# Cell.net
KiCad netlist of a schematic drawn in Altium Designer
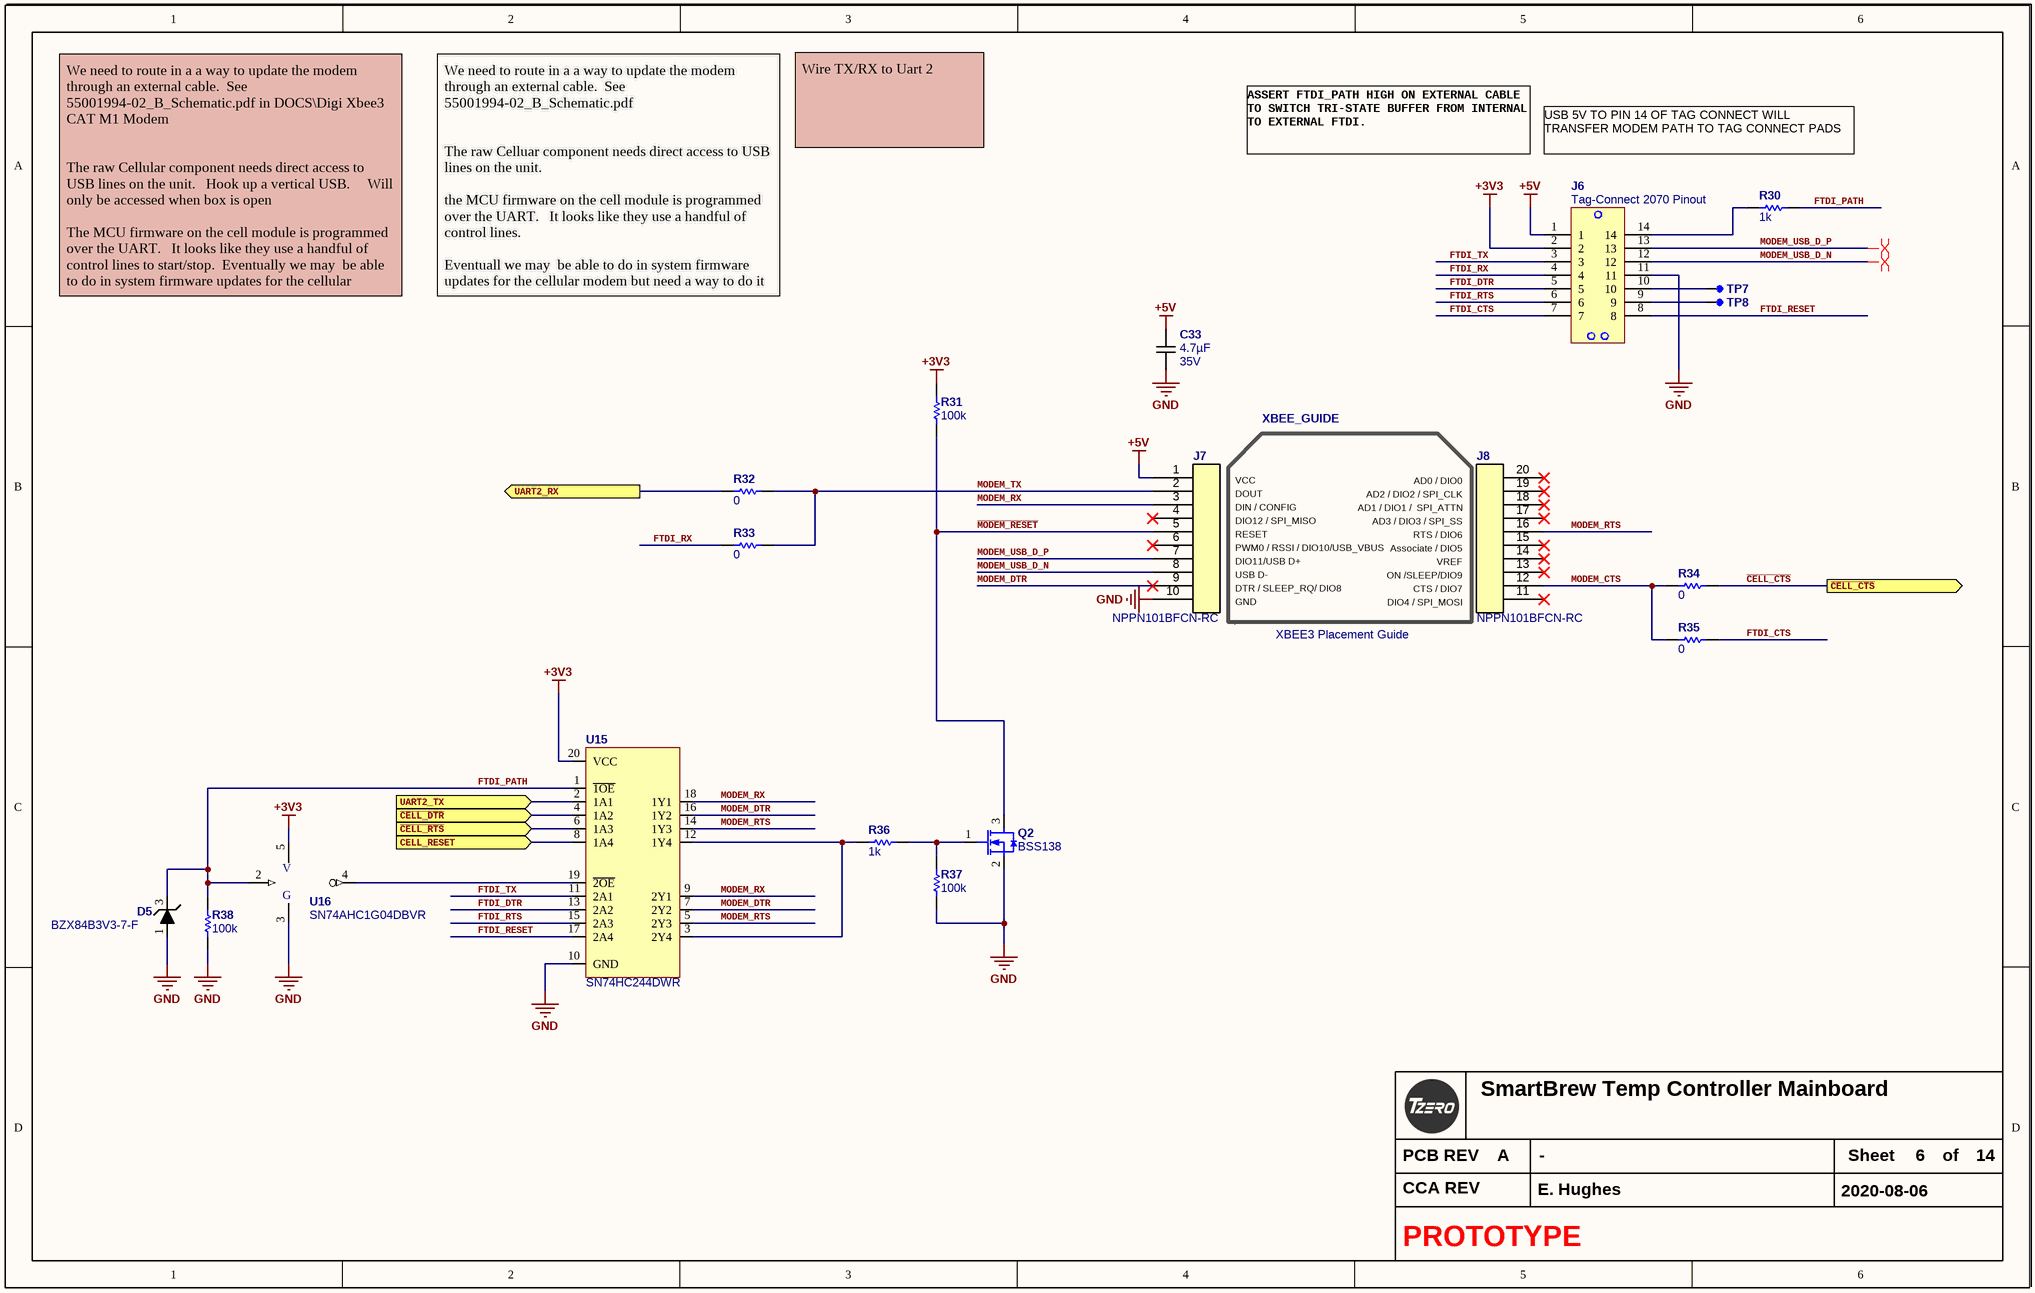
[diagram p0: Cell.SchDoc]

(export (version "E")
  (design (tool "Eeschema 10.0.6"))
  (components
    (comp (ref "C33")
      (value "4.7µF")
      (footprint "C0805_1.50MM_HD")
      (description "CAP CER 4.7UF 35V X7R 0805")
      (fields
        (field (name "MANUFACTURER PART NUMBER") "CGA4J1X7R1V475K125AE")
        (field (name "MANUFACTURER") "TDK Corporation")
        (field (name "VOLTAGE - RATED") "35V")
      )
      (libsource (lib "Capacitors - TDK- AEC-Q200") (part "C_2P_NP"))
    )
    (comp (ref "D5")
      (value "BZX84B3V3-7-F")
      (footprint "D_SOT-23-3_P")
      (description "DIODE ZENER 3.3V 300MW SOT23")
      (fields (field (name "MANUFACTURER") "Diodes Inc") (field (name "TOLERANCE") "±2%"))
      (libsource (lib "Diodes") (part "DZ_1A_3C"))
    )
    (comp (ref "J6")
      (value "Tag-Connect 2070 Pinout")
      (footprint "Tag Connect-N:TC2070")
      (libsource (lib "Tag Connect-N") (part "TC2070"))
    )
    (comp (ref "J7")
      (value "NPPN101BFCN-RC")
      (footprint "NPPN101BFCN-RC")
      (description "CONN RECEPT 2MM SINGLE STR 10POS")
      (fields (field (name "MANUFACTURER") "Sullins"))
      (libsource (lib "eConnector_Sullins_NPPN_2mm") (part "NPPN101BFCN-RC"))
    )
    (comp (ref "J8")
      (value "NPPN101BFCN-RC")
      (footprint "NPPN101BFCN-RC - 11-20")
      (description "CONN RECEPT 2MM SINGLE STR 10POS")
      (fields (field (name "MANUFACTURER") "Sullins"))
      (libsource (lib "eConnector_Sullins_NPPN_2mm") (part "NPPN101BFCN-RC_11-20"))
    )
    (comp (ref "Q2")
      (value "BSS138")
      (footprint "Integrated Circuits SMT-N:SOT23_Medium")
      (description "FAIRCHILD SEMICONDUCTOR - BSS138 - N CHANNEL MOSFET, 50V, 220mA SOT-23")
      (fields (field (name "MANUFACTURER") "FAIRCHILD SEMICONDUCTOR"))
      (libsource (lib "Transistors-N") (part "BSS138"))
    )
    (comp (ref "R30")
      (value "1k")
      (footprint "R0603_0.55MM_MD")
      (description "RES 1K OHM 1/10W 1% 0603 SMD")
      (fields
        (field (name "MANUFACTURER PART NUMBER") "ERJ-3EKF1001V")
        (field (name "MANUFACTURER") "Panasonic Electronic Components")
      )
      (libsource (lib "Resistors - Panasonic - AEC-Q200") (part "R_2P"))
    )
    (comp (ref "R31")
      (value "100k")
      (footprint "R0603_0.55MM_MD")
      (description "RES 100K OHM 1/10W 1% 0603 SMD")
      (fields
        (field (name "MANUFACTURER PART NUMBER") "ERJ-3EKF1003V")
        (field (name "MANUFACTURER") "Panasonic Electronic Components")
      )
      (libsource (lib "Resistors - Panasonic - AEC-Q200") (part "R_2P"))
    )
    (comp (ref "R32")
      (value "0")
      (footprint "R0603_0.55MM_MD")
      (description "RES 0.0 OHM 1/10W JUMP 0603 SMD")
      (fields
        (field (name "MANUFACTURER PART NUMBER") "ERJ-3GEY0R00V")
        (field (name "MANUFACTURER") "Panasonic Electronic Components")
      )
      (libsource (lib "Resistors - Panasonic - AEC-Q200") (part "R_2P"))
    )
    (comp (ref "R33")
      (value "0")
      (footprint "R0603_0.55MM_MD")
      (description "RES 0.0 OHM 1/10W JUMP 0603 SMD")
      (fields
        (field (name "MANUFACTURER PART NUMBER") "ERJ-3GEY0R00V")
        (field (name "MANUFACTURER") "Panasonic Electronic Components")
      )
      (libsource (lib "Resistors - Panasonic - AEC-Q200") (part "R_2P"))
    )
    (comp (ref "R34")
      (value "0")
      (footprint "R0603_0.55MM_MD")
      (description "RES 0.0 OHM 1/10W JUMP 0603 SMD")
      (fields
        (field (name "MANUFACTURER PART NUMBER") "ERJ-3GEY0R00V")
        (field (name "MANUFACTURER") "Panasonic Electronic Components")
      )
      (libsource (lib "Resistors - Panasonic - AEC-Q200") (part "R_2P"))
    )
    (comp (ref "R35")
      (value "0")
      (footprint "R0603_0.55MM_MD")
      (description "RES 0.0 OHM 1/10W JUMP 0603 SMD")
      (fields
        (field (name "MANUFACTURER PART NUMBER") "ERJ-3GEY0R00V")
        (field (name "MANUFACTURER") "Panasonic Electronic Components")
      )
      (libsource (lib "Resistors - Panasonic - AEC-Q200") (part "R_2P"))
    )
    (comp (ref "R36")
      (value "1k")
      (footprint "R0603_0.55MM_MD")
      (description "RES 1K OHM 1/10W 1% 0603 SMD")
      (fields
        (field (name "MANUFACTURER PART NUMBER") "ERJ-3EKF1001V")
        (field (name "MANUFACTURER") "Panasonic Electronic Components")
      )
      (libsource (lib "Resistors - Panasonic - AEC-Q200") (part "R_2P"))
    )
    (comp (ref "R37")
      (value "100k")
      (footprint "R0603_0.55MM_MD")
      (description "RES 100K OHM 1/10W 1% 0603 SMD")
      (fields
        (field (name "MANUFACTURER PART NUMBER") "ERJ-3EKF1003V")
        (field (name "MANUFACTURER") "Panasonic Electronic Components")
      )
      (libsource (lib "Resistors - Panasonic - AEC-Q200") (part "R_2P"))
    )
    (comp (ref "R38")
      (value "100k")
      (footprint "R0603_0.55MM_MD")
      (description "RES 100K OHM 1/10W 1% 0603 SMD")
      (fields
        (field (name "MANUFACTURER PART NUMBER") "ERJ-3EKF1003V")
        (field (name "MANUFACTURER") "Panasonic Electronic Components")
      )
      (libsource (lib "Resistors - Panasonic - AEC-Q200") (part "R_2P"))
    )
    (comp (ref "TP7")
      (value "~")
      (footprint "Test Points-N:TP_SMT_25_MIL_ROUND")
      (libsource (lib "Test Points-N") (part "TP SMT 25MIL"))
    )
    (comp (ref "TP8")
      (value "~")
      (footprint "Test Points-N:TP_SMT_25_MIL_ROUND")
      (libsource (lib "Test Points-N") (part "TP SMT 25MIL"))
    )
    (comp (ref "U15")
      (value "SN74HC244DWR")
      (footprint "Integrated Circuits SMT-N:SOIC-20-300_MEDIUM")
      (description "IC BUFF/DVR TRI-ST DUAL 20SOIC")
      (fields (field (name "MANUFACTURER") "Texas Instruments"))
      (libsource (lib "Logic-N") (part "SN74HC244DWR"))
    )
    (comp (ref "U16")
      (value "SN74AHC1G04DBVR")
      (footprint "TSOT-23-5")
      (description "IC SINGLE INVERTER GATE SOT23-5")
      (fields (field (name "MANUFACTURER") "Texas Instruments"))
      (libsource (lib "Logic-N") (part "SN74AHC1G04DBVR"))
    )
    (comp (ref "XBEE_GUIDE")
      (value "XBEE3 Placement Guide")
      (footprint "XBEE3_CELLULAR_PLACEMENT_GUIDE")
      (libsource (lib "eModule") (part "XBEE3_CELLULAR_PLACEMENT_GUIDE"))
    )
  )
  (nets
    (net (code "1") (name "+3V3") (class "Default")
      (node (ref "J6") (pin "2") (pinfunction "2_2") (pintype "passive"))
      (node (ref "R31") (pin "2") (pinfunction "2_2") (pintype "passive"))
      (node (ref "U15") (pin "20") (pinfunction "VCC_20") (pintype "passive"))
      (node (ref "U16") (pin "5") (pinfunction "VCC_5") (pintype "passive"))
    )
    (net (code "2") (name "+5V") (class "Default")
      (node (ref "C33") (pin "2") (pinfunction "1_2") (pintype "passive"))
      (node (ref "J6") (pin "1") (pinfunction "1_1") (pintype "passive"))
      (node (ref "J7") (pin "1") (pinfunction "1_1") (pintype "passive"))
    )
    (net (code "3") (name "/CELL_CTS") (class "Default")
      (node (ref "R34") (pin "1") (pinfunction "1_1") (pintype "passive"))
    )
    (net (code "4") (name "/CELL_DTR") (class "Default")
      (node (ref "U15") (pin "4") (pinfunction "1A2_4") (pintype "passive"))
    )
    (net (code "5") (name "/CELL_RESET") (class "Default")
      (node (ref "U15") (pin "8") (pinfunction "1A4_8") (pintype "passive"))
    )
    (net (code "6") (name "/CELL_RTS") (class "Default")
      (node (ref "U15") (pin "6") (pinfunction "1A3_6") (pintype "passive"))
    )
    (net (code "7") (name "/FTDI_CTS") (class "Default")
      (node (ref "J6") (pin "7") (pinfunction "7_7") (pintype "passive"))
      (node (ref "R35") (pin "1") (pinfunction "1_1") (pintype "passive"))
    )
    (net (code "8") (name "/FTDI_DTR") (class "Default")
      (node (ref "J6") (pin "5") (pinfunction "5_5") (pintype "passive"))
      (node (ref "U15") (pin "13") (pinfunction "2A2_13") (pintype "passive"))
    )
    (net (code "9") (name "/FTDI_PATH") (class "Default")
      (node (ref "D5") (pin "3") (pinfunction "K_3") (pintype "passive"))
      (node (ref "R30") (pin "1") (pinfunction "1_1") (pintype "passive"))
      (node (ref "R38") (pin "2") (pinfunction "2_2") (pintype "passive"))
      (node (ref "U15") (pin "1") (pinfunction "1OE_1") (pintype "passive"))
      (node (ref "U16") (pin "2") (pinfunction "A_2") (pintype "input"))
    )
    (net (code "10") (name "/FTDI_RESET") (class "Default")
      (node (ref "J6") (pin "8") (pinfunction "8_8") (pintype "passive"))
      (node (ref "U15") (pin "17") (pinfunction "2A4_17") (pintype "passive"))
    )
    (net (code "11") (name "/FTDI_RTS") (class "Default")
      (node (ref "J6") (pin "6") (pinfunction "6_6") (pintype "passive"))
      (node (ref "U15") (pin "15") (pinfunction "2A3_15") (pintype "passive"))
    )
    (net (code "12") (name "/FTDI_RX") (class "Default")
      (node (ref "J6") (pin "4") (pinfunction "4_4") (pintype "passive"))
      (node (ref "R33") (pin "2") (pinfunction "2_2") (pintype "passive"))
    )
    (net (code "13") (name "/FTDI_TX") (class "Default")
      (node (ref "J6") (pin "3") (pinfunction "3_3") (pintype "passive"))
      (node (ref "U15") (pin "11") (pinfunction "2A1_11") (pintype "passive"))
    )
    (net (code "14") (name "/MODEM_CTS") (class "Default")
      (node (ref "J8") (pin "12") (pinfunction "12_12") (pintype "passive"))
      (node (ref "R34") (pin "2") (pinfunction "2_2") (pintype "passive"))
      (node (ref "R35") (pin "2") (pinfunction "2_2") (pintype "passive"))
    )
    (net (code "15") (name "/MODEM_DTR") (class "Default")
      (node (ref "J7") (pin "9") (pinfunction "9_9") (pintype "passive"))
      (node (ref "U15") (pin "16") (pinfunction "1Y2_16") (pintype "passive"))
      (node (ref "U15") (pin "7") (pinfunction "2Y2_7") (pintype "passive"))
    )
    (net (code "16") (name "/MODEM_RESET") (class "Default")
      (node (ref "J7") (pin "5") (pinfunction "5_5") (pintype "passive"))
      (node (ref "Q2") (pin "3") (pinfunction "D_3") (pintype "passive"))
      (node (ref "R31") (pin "1") (pinfunction "1_1") (pintype "passive"))
    )
    (net (code "17") (name "/MODEM_RTS") (class "Default")
      (node (ref "J8") (pin "16") (pinfunction "16_16") (pintype "passive"))
      (node (ref "U15") (pin "14") (pinfunction "1Y3_14") (pintype "passive"))
      (node (ref "U15") (pin "5") (pinfunction "2Y3_5") (pintype "passive"))
    )
    (net (code "18") (name "/MODEM_RX") (class "Default")
      (node (ref "J7") (pin "3") (pinfunction "3_3") (pintype "passive"))
      (node (ref "U15") (pin "18") (pinfunction "1Y1_18") (pintype "passive"))
      (node (ref "U15") (pin "9") (pinfunction "2Y1_9") (pintype "passive"))
    )
    (net (code "19") (name "/MODEM_TX") (class "Default")
      (node (ref "J7") (pin "2") (pinfunction "2_2") (pintype "passive"))
      (node (ref "R32") (pin "1") (pinfunction "1_1") (pintype "passive"))
      (node (ref "R33") (pin "1") (pinfunction "1_1") (pintype "passive"))
    )
    (net (code "20") (name "/MODEM_USB_D_N") (class "Default")
      (node (ref "J6") (pin "12") (pinfunction "12_12") (pintype "passive"))
      (node (ref "J7") (pin "8") (pinfunction "8_8") (pintype "passive"))
    )
    (net (code "21") (name "/MODEM_USB_D_P") (class "Default")
      (node (ref "J6") (pin "13") (pinfunction "13_13") (pintype "passive"))
      (node (ref "J7") (pin "7") (pinfunction "7_7") (pintype "passive"))
    )
    (net (code "22") (name "/UART2_RX") (class "Default")
      (node (ref "R32") (pin "2") (pinfunction "2_2") (pintype "passive"))
    )
    (net (code "23") (name "/UART2_TX") (class "Default")
      (node (ref "U15") (pin "2") (pinfunction "1A1_2") (pintype "passive"))
    )
    (net (code "24") (name "GND") (class "Default")
      (node (ref "C33") (pin "1") (pinfunction "1_1") (pintype "passive"))
      (node (ref "D5") (pin "1") (pinfunction "A_1") (pintype "passive"))
      (node (ref "J6") (pin "11") (pinfunction "11_11") (pintype "passive"))
      (node (ref "J7") (pin "10") (pinfunction "10_10") (pintype "passive"))
      (node (ref "Q2") (pin "2") (pinfunction "S_2") (pintype "passive"))
      (node (ref "R37") (pin "1") (pinfunction "1_1") (pintype "passive"))
      (node (ref "R38") (pin "1") (pinfunction "1_1") (pintype "passive"))
      (node (ref "U15") (pin "10") (pinfunction "GND_10") (pintype "passive"))
      (node (ref "U16") (pin "3") (pinfunction "GND_3") (pintype "passive"))
    )
    (net (code "25") (name "Net-(J6-Pad9)") (class "Default")
      (node (ref "J6") (pin "9") (pinfunction "9_9") (pintype "passive"))
      (node (ref "TP8") (pin "1") (pinfunction "1_1") (pintype "passive"))
    )
    (net (code "26") (name "Net-(J6-Pad10)") (class "Default")
      (node (ref "J6") (pin "10") (pinfunction "10_10") (pintype "passive"))
      (node (ref "TP7") (pin "1") (pinfunction "1_1") (pintype "passive"))
    )
    (net (code "27") (name "Net-(J6-Pad14)") (class "Default")
      (node (ref "J6") (pin "14") (pinfunction "14_14") (pintype "passive"))
      (node (ref "R30") (pin "2") (pinfunction "2_2") (pintype "passive"))
    )
    (net (code "28") (name "Net-(Q2-G)") (class "Default")
      (node (ref "Q2") (pin "1") (pinfunction "G_1") (pintype "passive"))
      (node (ref "R36") (pin "1") (pinfunction "1_1") (pintype "passive"))
      (node (ref "R37") (pin "2") (pinfunction "2_2") (pintype "passive"))
    )
    (net (code "29") (name "Net-(U15-1Y4)") (class "Default")
      (node (ref "R36") (pin "2") (pinfunction "2_2") (pintype "passive"))
      (node (ref "U15") (pin "12") (pinfunction "1Y4_12") (pintype "passive"))
      (node (ref "U15") (pin "3") (pinfunction "2Y4_3") (pintype "passive"))
    )
    (net (code "30") (name "Net-(U15-2OE)") (class "Default")
      (node (ref "U15") (pin "19") (pinfunction "2OE_19") (pintype "passive"))
      (node (ref "U16") (pin "4") (pinfunction "Y_4") (pintype "output"))
    )
    (net (code "31") (name "unconnected-(J7-Pad4)") (class "Default")
      (node (ref "J7") (pin "4") (pinfunction "4_4") (pintype "passive+no_connect"))
    )
    (net (code "32") (name "unconnected-(J7-Pad6)") (class "Default")
      (node (ref "J7") (pin "6") (pinfunction "6_6") (pintype "passive+no_connect"))
    )
    (net (code "33") (name "unconnected-(J8-Pad11)") (class "Default")
      (node (ref "J8") (pin "11") (pinfunction "11_11") (pintype "passive+no_connect"))
    )
    (net (code "34") (name "unconnected-(J8-Pad13)") (class "Default")
      (node (ref "J8") (pin "13") (pinfunction "13_13") (pintype "passive+no_connect"))
    )
    (net (code "35") (name "unconnected-(J8-Pad14)") (class "Default")
      (node (ref "J8") (pin "14") (pinfunction "14_14") (pintype "passive+no_connect"))
    )
    (net (code "36") (name "unconnected-(J8-Pad15)") (class "Default")
      (node (ref "J8") (pin "15") (pinfunction "15_15") (pintype "passive+no_connect"))
    )
    (net (code "37") (name "unconnected-(J8-Pad17)") (class "Default")
      (node (ref "J8") (pin "17") (pinfunction "17_17") (pintype "passive+no_connect"))
    )
    (net (code "38") (name "unconnected-(J8-Pad18)") (class "Default")
      (node (ref "J8") (pin "18") (pinfunction "18_18") (pintype "passive+no_connect"))
    )
    (net (code "39") (name "unconnected-(J8-Pad19)") (class "Default")
      (node (ref "J8") (pin "19") (pinfunction "19_19") (pintype "passive+no_connect"))
    )
    (net (code "40") (name "unconnected-(J8-Pad20)") (class "Default")
      (node (ref "J8") (pin "20") (pinfunction "20_20") (pintype "passive+no_connect"))
    )
  )
)
